# RS485_CAN.net
KiCad netlist of a schematic drawn in Altium Designer
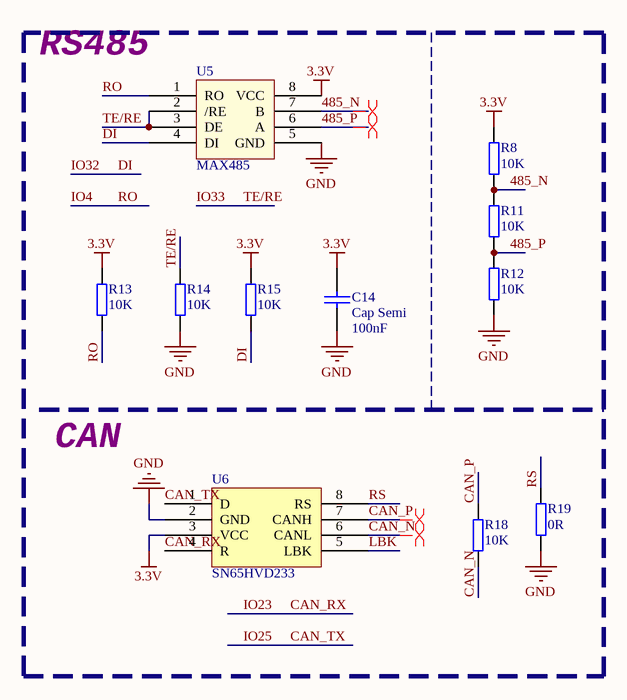
[diagram p0: RS485_CAN.SchDoc]

(export (version "E")
  (design (tool "Eeschema 10.0.6"))
  (components
    (comp (ref "C14")
      (value "Cap Semi")
      (footprint "SMT0603")
      (description "CAP SM 0603 X7R 100nF 10%")
      (fields (field (name "TOLERANCE") "±10%") (field (name "ALTIUM_VALUE") "100nF"))
      (libsource (lib "electronpowered") (part "CAP-SM-0603-X7R-100nF"))
    )
    (comp (ref "R8")
      (value "10K")
      (footprint "SMT0603")
      (description "RES SM 0603 10K")
      (fields (field (name "Comment") "Resistor"))
      (libsource (lib "electronpowered") (part "RES-SM-0603-10K"))
    )
    (comp (ref "R11")
      (value "10K")
      (footprint "SMT0603")
      (description "RES SM 0603 10K")
      (fields (field (name "Comment") "Resistor"))
      (libsource (lib "electronpowered") (part "RES-SM-0603-10K"))
    )
    (comp (ref "R12")
      (value "10K")
      (footprint "SMT0603")
      (description "RES SM 0603 10K")
      (fields (field (name "Comment") "Resistor"))
      (libsource (lib "electronpowered") (part "RES-SM-0603-10K"))
    )
    (comp (ref "R13")
      (value "10K")
      (footprint "SMT0603")
      (description "RES SM 0603 10K")
      (fields (field (name "Comment") "Resistor"))
      (libsource (lib "electronpowered") (part "RES-SM-0603-10K"))
    )
    (comp (ref "R14")
      (value "10K")
      (footprint "SMT0603")
      (description "RES SM 0603 10K")
      (fields (field (name "Comment") "Resistor"))
      (libsource (lib "electronpowered") (part "RES-SM-0603-10K"))
    )
    (comp (ref "R15")
      (value "10K")
      (footprint "SMT0603")
      (description "RES SM 0603 10K")
      (fields (field (name "Comment") "Resistor"))
      (libsource (lib "electronpowered") (part "RES-SM-0603-10K"))
    )
    (comp (ref "R18")
      (value "10K")
      (footprint "SMT0603")
      (description "RES SM 0603 10K")
      (fields (field (name "Comment") "Resistor"))
      (libsource (lib "electronpowered") (part "RES-SM-0603-10K"))
    )
    (comp (ref "R19")
      (value "0R")
      (footprint "SMT0603")
      (description "RES SM 0603 10K")
      (fields (field (name "Comment") "Resistor"))
      (libsource (lib "electronpowered") (part "RES-SM-0603-10K"))
    )
    (comp (ref "U5") (value "MAX485") (footprint "SOP8") (libsource (lib "RASHBERRY_EXTERN") (part "MAX485")))
    (comp (ref "U6")
      (value "SN65HVD233")
      (footprint "PCBComponent_1")
      (libsource (lib "SN65HVD233") (part "SN65HVD233"))
    )
  )
  (nets
    (net (code "1") (name "/485_N") (class "Default")
      (node (ref "R11") (pin "2") (pinfunction "2_2") (pintype "passive"))
      (node (ref "R8") (pin "1") (pinfunction "1_1") (pintype "passive"))
      (node (ref "U5") (pin "7") (pinfunction "B_7") (pintype "passive"))
    )
    (net (code "2") (name "/485_P") (class "Default")
      (node (ref "R11") (pin "1") (pinfunction "1_1") (pintype "passive"))
      (node (ref "R12") (pin "2") (pinfunction "2_2") (pintype "passive"))
      (node (ref "U5") (pin "6") (pinfunction "A_6") (pintype "passive"))
    )
    (net (code "3") (name "/CAN_N") (class "Default")
      (node (ref "R18") (pin "1") (pinfunction "1_1") (pintype "passive"))
      (node (ref "U6") (pin "6") (pinfunction "CANL_6") (pintype "passive"))
    )
    (net (code "4") (name "/CAN_P") (class "Default")
      (node (ref "R18") (pin "2") (pinfunction "2_2") (pintype "passive"))
      (node (ref "U6") (pin "7") (pinfunction "CANH_7") (pintype "passive"))
    )
    (net (code "5") (name "/CAN_RX") (class "Default")
      (node (ref "U6") (pin "4") (pinfunction "R_4") (pintype "passive"))
    )
    (net (code "6") (name "/CAN_TX") (class "Default")
      (node (ref "U6") (pin "1") (pinfunction "D_1") (pintype "passive"))
    )
    (net (code "7") (name "/DI") (class "Default")
      (node (ref "R15") (pin "1") (pinfunction "1_1") (pintype "passive"))
      (node (ref "U5") (pin "4") (pinfunction "DI_4") (pintype "passive"))
    )
    (net (code "8") (name "/IO4") (class "Default")
      (node (ref "R13") (pin "1") (pinfunction "1_1") (pintype "passive"))
      (node (ref "U5") (pin "1") (pinfunction "RO_1") (pintype "passive"))
    )
    (net (code "9") (name "/IO33") (class "Default")
      (node (ref "R14") (pin "2") (pinfunction "2_2") (pintype "passive"))
      (node (ref "U5") (pin "2") (pinfunction "/RE_2") (pintype "passive"))
      (node (ref "U5") (pin "3") (pinfunction "DE_3") (pintype "passive"))
    )
    (net (code "10") (name "/LBK") (class "Default")
      (node (ref "U6") (pin "5") (pinfunction "LBK_5") (pintype "passive"))
    )
    (net (code "11") (name "/RS") (class "Default")
      (node (ref "R19") (pin "2") (pinfunction "2_2") (pintype "passive"))
      (node (ref "U6") (pin "8") (pinfunction "RS_8") (pintype "passive"))
    )
    (net (code "12") (name "3.3V") (class "Default")
      (node (ref "C14") (pin "2") (pinfunction "2_2") (pintype "passive"))
      (node (ref "R13") (pin "2") (pinfunction "2_2") (pintype "passive"))
      (node (ref "R15") (pin "2") (pinfunction "2_2") (pintype "passive"))
      (node (ref "R8") (pin "2") (pinfunction "2_2") (pintype "passive"))
      (node (ref "U5") (pin "8") (pinfunction "VCC_8") (pintype "passive"))
      (node (ref "U6") (pin "3") (pinfunction "VCC_3") (pintype "passive"))
    )
    (net (code "13") (name "GND") (class "Default")
      (node (ref "C14") (pin "1") (pinfunction "1_1") (pintype "passive"))
      (node (ref "R12") (pin "1") (pinfunction "1_1") (pintype "passive"))
      (node (ref "R14") (pin "1") (pinfunction "1_1") (pintype "passive"))
      (node (ref "R19") (pin "1") (pinfunction "1_1") (pintype "passive"))
      (node (ref "U5") (pin "5") (pinfunction "GND_5") (pintype "passive"))
      (node (ref "U6") (pin "2") (pinfunction "GND_2") (pintype "passive"))
    )
  )
)
